# NPN_Cell.net
KiCad netlist of a schematic drawn in Altium Designer
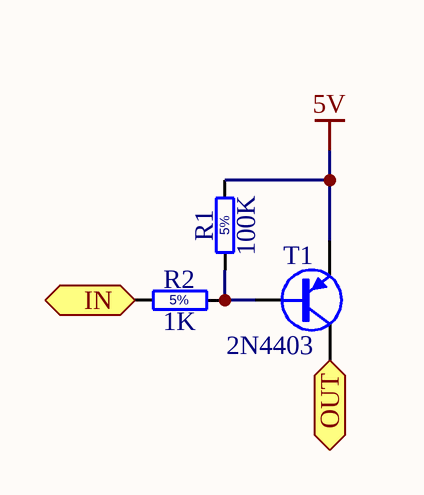
[diagram p0: NPN_Cell.SchDoc]

(export (version "E")
  (design (tool "Eeschema 10.0.6"))
  (components
    (comp (ref "R1")
      (value "100K")
      (footprint "RES_ARCOL_RCC025")
      (description "Resistor - 5%")
      (fields
        (field (name "PART NUMBER") "RCF_5K1_5%_0.25W_+10-6PPM_ARCOL_RCC025")
        (field (name "POWER") "0.25W")
        (field (name "AUTHOR") "CERN DEM JLC")
      )
      (libsource (lib "Resistors") (part "Resistor - 5%"))
    )
    (comp (ref "R2")
      (value "1K")
      (footprint "RES_ARCOL_RCC025")
      (description "Resistor - 5%")
      (fields
        (field (name "PART NUMBER") "RCF_5K1_5%_0.25W_+10-6PPM_ARCOL_RCC025")
        (field (name "POWER") "0.25W")
        (field (name "AUTHOR") "CERN DEM JLC")
      )
      (libsource (lib "Resistors") (part "Resistor - 5%"))
    )
    (comp (ref "T1")
      (value "2N4403")
      (footprint "TO-92AA-P254")
      (description "PNP Transistor")
      (fields
        (field (name "PART NUMBER") "2N3906RL1G")
        (field (name "MANUFACTURER") "ON SEMICONDUCTOR")
        (field (name "AUTHOR") "CERN DEM JLC")
      )
      (libsource (lib "ICs And Semiconductors") (part "PNP E1 B2 C3"))
    )
  )
  (nets
    (net (code "1") (name "/IN") (class "Default")
      (node (ref "R2") (pin "1") (pinfunction "1_1") (pintype "passive"))
    )
    (net (code "2") (name "/OUT") (class "Default")
      (node (ref "T1") (pin "3") (pinfunction "C_3") (pintype "passive"))
    )
    (net (code "3") (name "5V") (class "Default")
      (node (ref "R1") (pin "2") (pinfunction "2_2") (pintype "passive"))
      (node (ref "T1") (pin "1") (pinfunction "E_1") (pintype "passive"))
    )
    (net (code "4") (name "Net-(T1-B)") (class "Default")
      (node (ref "R1") (pin "1") (pinfunction "1_1") (pintype "passive"))
      (node (ref "R2") (pin "2") (pinfunction "2_2") (pintype "passive"))
      (node (ref "T1") (pin "2") (pinfunction "B_2") (pintype "passive"))
    )
  )
)
